# pecl_termination.net
KiCad netlist of a schematic drawn in EAGLE
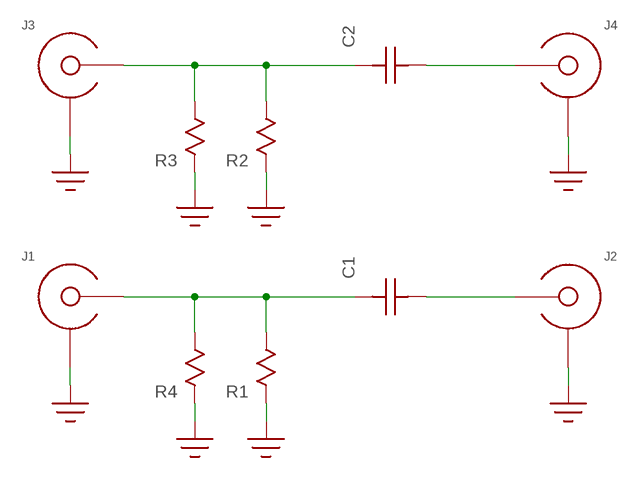
[diagram p0: schematic, sheet 1]

(export (version "E")
  (design (tool "Eeschema 10.0.6"))
  (components
    (comp (ref "C1")
      (value "C0805")
      (footprint "eagle-import:0805")
      (libsource (lib "eagle-import") (part "C0805"))
    )
    (comp (ref "C2")
      (value "C0805")
      (footprint "eagle-import:0805")
      (libsource (lib "eagle-import") (part "C0805"))
    )
    (comp (ref "J1")
      (value "EDGE_LAUNCH_JACK")
      (footprint "eagle-import:EDGE_LAUNCH_RF_CON")
      (libsource (lib "eagle-import") (part "EDGE_LAUNCH_JACK"))
    )
    (comp (ref "J2")
      (value "EDGE_LAUNCH_JACK")
      (footprint "eagle-import:EDGE_LAUNCH_RF_CON")
      (libsource (lib "eagle-import") (part "EDGE_LAUNCH_JACK"))
    )
    (comp (ref "J3")
      (value "EDGE_LAUNCH_JACK")
      (footprint "eagle-import:EDGE_LAUNCH_RF_CON")
      (libsource (lib "eagle-import") (part "EDGE_LAUNCH_JACK"))
    )
    (comp (ref "J4")
      (value "EDGE_LAUNCH_JACK")
      (footprint "eagle-import:EDGE_LAUNCH_RF_CON")
      (libsource (lib "eagle-import") (part "EDGE_LAUNCH_JACK"))
    )
    (comp (ref "R1")
      (value "R0805")
      (footprint "eagle-import:R0805")
      (libsource (lib "eagle-import") (part "R0805"))
    )
    (comp (ref "R2")
      (value "R0805")
      (footprint "eagle-import:R0805")
      (libsource (lib "eagle-import") (part "R0805"))
    )
    (comp (ref "R3")
      (value "R0805")
      (footprint "eagle-import:R0805")
      (libsource (lib "eagle-import") (part "R0805"))
    )
    (comp (ref "R4")
      (value "R0805")
      (footprint "eagle-import:R0805")
      (libsource (lib "eagle-import") (part "R0805"))
    )
  )
  (nets
    (net (code "1") (name "GND") (class "Default")
      (node (ref "J1") (pin "GND@1") (pinfunction "SHIELD_GND@1") (pintype "bidirectional"))
      (node (ref "J1") (pin "GND@10") (pinfunction "SHIELD_GND@10") (pintype "bidirectional"))
      (node (ref "J1") (pin "GND@11") (pinfunction "SHIELD_GND@11") (pintype "bidirectional"))
      (node (ref "J1") (pin "GND@12") (pinfunction "SHIELD_GND@12") (pintype "bidirectional"))
      (node (ref "J1") (pin "GND@2") (pinfunction "SHIELD_GND@2") (pintype "bidirectional"))
      (node (ref "J1") (pin "GND@3") (pinfunction "SHIELD_GND@3") (pintype "bidirectional"))
      (node (ref "J1") (pin "GND@4") (pinfunction "SHIELD_GND@4") (pintype "bidirectional"))
      (node (ref "J1") (pin "GND@5") (pinfunction "SHIELD_GND@5") (pintype "bidirectional"))
      (node (ref "J1") (pin "GND@6") (pinfunction "SHIELD_GND@6") (pintype "bidirectional"))
      (node (ref "J1") (pin "GND@7") (pinfunction "SHIELD_GND@7") (pintype "bidirectional"))
      (node (ref "J1") (pin "GND@8") (pinfunction "SHIELD_GND@8") (pintype "bidirectional"))
      (node (ref "J1") (pin "GND@9") (pinfunction "SHIELD_GND@9") (pintype "bidirectional"))
      (node (ref "J1") (pin "SHIELD@1") (pinfunction "SHIELD_SHIELD@1") (pintype "bidirectional"))
      (node (ref "J1") (pin "SHIELD@2") (pinfunction "SHIELD_SHIELD@2") (pintype "bidirectional"))
      (node (ref "J2") (pin "GND@1") (pinfunction "SHIELD_GND@1") (pintype "bidirectional"))
      (node (ref "J2") (pin "GND@10") (pinfunction "SHIELD_GND@10") (pintype "bidirectional"))
      (node (ref "J2") (pin "GND@11") (pinfunction "SHIELD_GND@11") (pintype "bidirectional"))
      (node (ref "J2") (pin "GND@12") (pinfunction "SHIELD_GND@12") (pintype "bidirectional"))
      (node (ref "J2") (pin "GND@2") (pinfunction "SHIELD_GND@2") (pintype "bidirectional"))
      (node (ref "J2") (pin "GND@3") (pinfunction "SHIELD_GND@3") (pintype "bidirectional"))
      (node (ref "J2") (pin "GND@4") (pinfunction "SHIELD_GND@4") (pintype "bidirectional"))
      (node (ref "J2") (pin "GND@5") (pinfunction "SHIELD_GND@5") (pintype "bidirectional"))
      (node (ref "J2") (pin "GND@6") (pinfunction "SHIELD_GND@6") (pintype "bidirectional"))
      (node (ref "J2") (pin "GND@7") (pinfunction "SHIELD_GND@7") (pintype "bidirectional"))
      (node (ref "J2") (pin "GND@8") (pinfunction "SHIELD_GND@8") (pintype "bidirectional"))
      (node (ref "J2") (pin "GND@9") (pinfunction "SHIELD_GND@9") (pintype "bidirectional"))
      (node (ref "J2") (pin "SHIELD@1") (pinfunction "SHIELD_SHIELD@1") (pintype "bidirectional"))
      (node (ref "J2") (pin "SHIELD@2") (pinfunction "SHIELD_SHIELD@2") (pintype "bidirectional"))
      (node (ref "J3") (pin "GND@1") (pinfunction "SHIELD_GND@1") (pintype "bidirectional"))
      (node (ref "J3") (pin "GND@10") (pinfunction "SHIELD_GND@10") (pintype "bidirectional"))
      (node (ref "J3") (pin "GND@11") (pinfunction "SHIELD_GND@11") (pintype "bidirectional"))
      (node (ref "J3") (pin "GND@12") (pinfunction "SHIELD_GND@12") (pintype "bidirectional"))
      (node (ref "J3") (pin "GND@2") (pinfunction "SHIELD_GND@2") (pintype "bidirectional"))
      (node (ref "J3") (pin "GND@3") (pinfunction "SHIELD_GND@3") (pintype "bidirectional"))
      (node (ref "J3") (pin "GND@4") (pinfunction "SHIELD_GND@4") (pintype "bidirectional"))
      (node (ref "J3") (pin "GND@5") (pinfunction "SHIELD_GND@5") (pintype "bidirectional"))
      (node (ref "J3") (pin "GND@6") (pinfunction "SHIELD_GND@6") (pintype "bidirectional"))
      (node (ref "J3") (pin "GND@7") (pinfunction "SHIELD_GND@7") (pintype "bidirectional"))
      (node (ref "J3") (pin "GND@8") (pinfunction "SHIELD_GND@8") (pintype "bidirectional"))
      (node (ref "J3") (pin "GND@9") (pinfunction "SHIELD_GND@9") (pintype "bidirectional"))
      (node (ref "J3") (pin "SHIELD@1") (pinfunction "SHIELD_SHIELD@1") (pintype "bidirectional"))
      (node (ref "J3") (pin "SHIELD@2") (pinfunction "SHIELD_SHIELD@2") (pintype "bidirectional"))
      (node (ref "J4") (pin "GND@1") (pinfunction "SHIELD_GND@1") (pintype "bidirectional"))
      (node (ref "J4") (pin "GND@10") (pinfunction "SHIELD_GND@10") (pintype "bidirectional"))
      (node (ref "J4") (pin "GND@11") (pinfunction "SHIELD_GND@11") (pintype "bidirectional"))
      (node (ref "J4") (pin "GND@12") (pinfunction "SHIELD_GND@12") (pintype "bidirectional"))
      (node (ref "J4") (pin "GND@2") (pinfunction "SHIELD_GND@2") (pintype "bidirectional"))
      (node (ref "J4") (pin "GND@3") (pinfunction "SHIELD_GND@3") (pintype "bidirectional"))
      (node (ref "J4") (pin "GND@4") (pinfunction "SHIELD_GND@4") (pintype "bidirectional"))
      (node (ref "J4") (pin "GND@5") (pinfunction "SHIELD_GND@5") (pintype "bidirectional"))
      (node (ref "J4") (pin "GND@6") (pinfunction "SHIELD_GND@6") (pintype "bidirectional"))
      (node (ref "J4") (pin "GND@7") (pinfunction "SHIELD_GND@7") (pintype "bidirectional"))
      (node (ref "J4") (pin "GND@8") (pinfunction "SHIELD_GND@8") (pintype "bidirectional"))
      (node (ref "J4") (pin "GND@9") (pinfunction "SHIELD_GND@9") (pintype "bidirectional"))
      (node (ref "J4") (pin "SHIELD@1") (pinfunction "SHIELD_SHIELD@1") (pintype "bidirectional"))
      (node (ref "J4") (pin "SHIELD@2") (pinfunction "SHIELD_SHIELD@2") (pintype "bidirectional"))
      (node (ref "R1") (pin "P$1") (pinfunction "P$3_P$1") (pintype "bidirectional"))
      (node (ref "R2") (pin "P$1") (pinfunction "P$3_P$1") (pintype "bidirectional"))
      (node (ref "R3") (pin "P$1") (pinfunction "P$3_P$1") (pintype "bidirectional"))
      (node (ref "R4") (pin "P$1") (pinfunction "P$3_P$1") (pintype "bidirectional"))
    )
    (net (code "2") (name "Net-(C1-PadP$1)") (class "Default")
      (node (ref "C1") (pin "P$1") (pinfunction "P$1_P$1") (pintype "bidirectional"))
      (node (ref "J2") (pin "CENTER") (pinfunction "CENTER_CENTER") (pintype "bidirectional"))
    )
    (net (code "3") (name "Net-(C2-PadP$1)") (class "Default")
      (node (ref "C2") (pin "P$1") (pinfunction "P$1_P$1") (pintype "bidirectional"))
      (node (ref "J4") (pin "CENTER") (pinfunction "CENTER_CENTER") (pintype "bidirectional"))
    )
    (net (code "4") (name "Net-(R1-P$4)") (class "Default")
      (node (ref "C1") (pin "P$2") (pinfunction "P$2_P$2") (pintype "bidirectional"))
      (node (ref "J1") (pin "CENTER") (pinfunction "CENTER_CENTER") (pintype "bidirectional"))
      (node (ref "R1") (pin "P$2") (pinfunction "P$4_P$2") (pintype "bidirectional"))
      (node (ref "R4") (pin "P$2") (pinfunction "P$4_P$2") (pintype "bidirectional"))
    )
    (net (code "5") (name "Net-(R2-P$4)") (class "Default")
      (node (ref "C2") (pin "P$2") (pinfunction "P$2_P$2") (pintype "bidirectional"))
      (node (ref "J3") (pin "CENTER") (pinfunction "CENTER_CENTER") (pintype "bidirectional"))
      (node (ref "R2") (pin "P$2") (pinfunction "P$4_P$2") (pintype "bidirectional"))
      (node (ref "R3") (pin "P$2") (pinfunction "P$4_P$2") (pintype "bidirectional"))
    )
  )
)
